# SiLPA_HE_RF_channel_preamp.net
KiCad netlist of a schematic drawn in Altium Designer
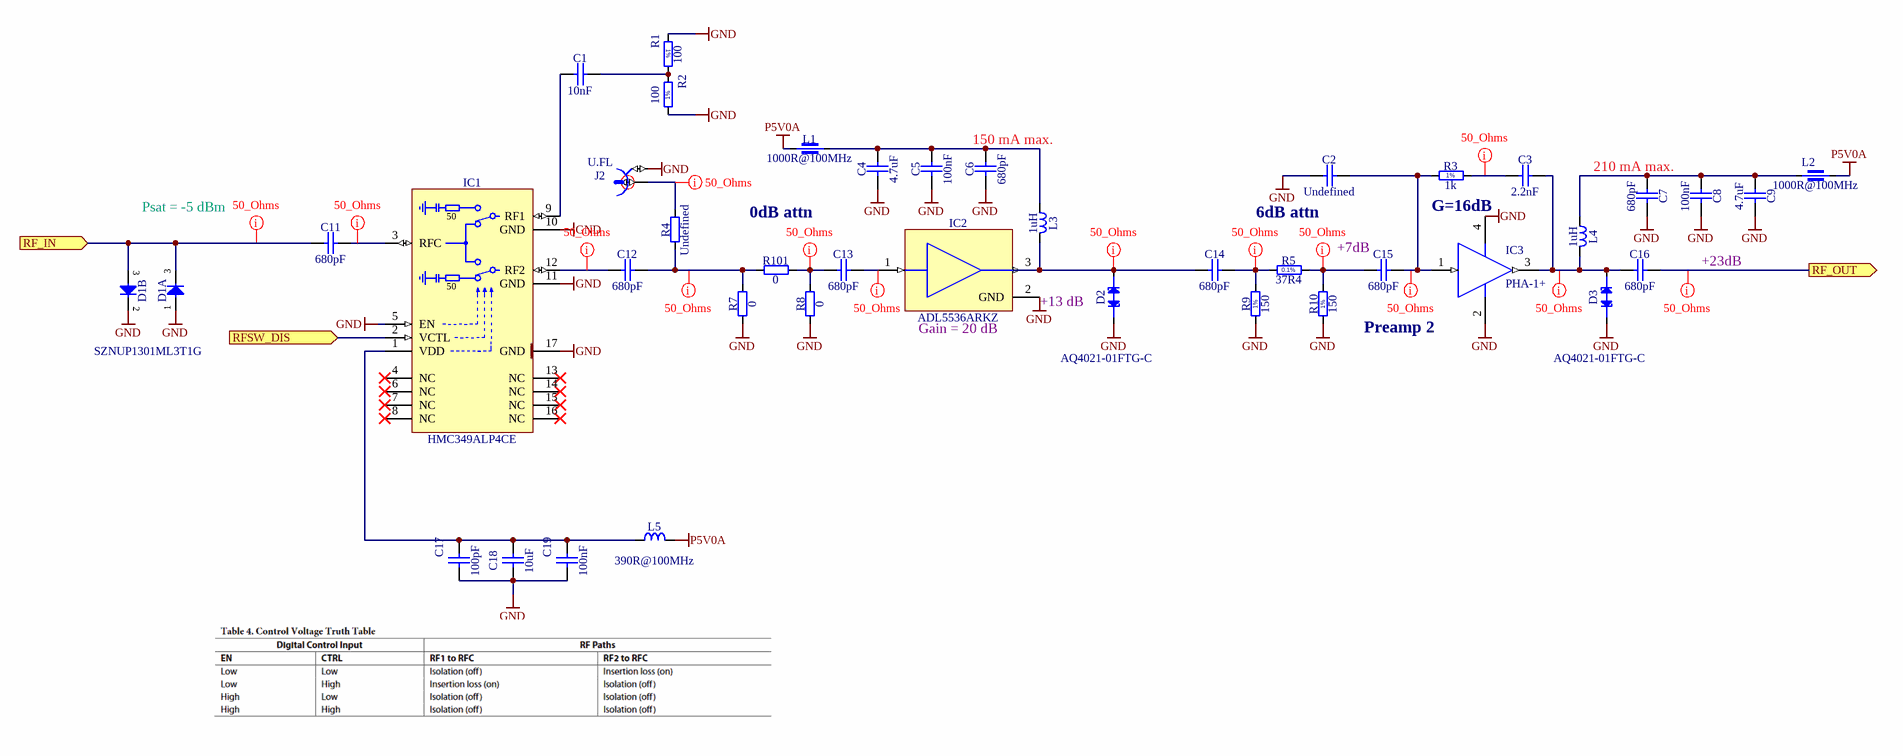
[diagram p0: SiLPA_HE_RF_channel_preamp.SchDoc]

(export (version "E")
  (design (tool "Eeschema 10.0.6"))
  (components
    (comp (ref "C1")
      (value "10nF")
      (footprint "CAPC1005X55N")
      (description "Non-polarised capacitor")
      (fields
        (field (name "PART NUMBER") "CC0402_10NF_16V_10%_X7R")
        (field (name "VOLTAGE") "16V")
        (field (name "AUTHOR") "CERN DEM JLC")
      )
      (libsource (lib "Capacitors") (part "Capacitor - non polarized"))
    )
    (comp (ref "C2")
      (value "Undefined")
      (footprint "CAPC1608X90N")
      (description "Non-polarised capacitor")
      (fields (field (name "PART NUMBER") "CC0603_NO-VALUE") (field (name "AUTHOR") "CERN DEM MR"))
      (libsource (lib "Capacitors") (part "Capacitor - non polarized"))
    )
    (comp (ref "C3")
      (value "2.2nF")
      (footprint "CAPC1608X87N")
      (description "Non-polarised capacitor")
      (fields
        (field (name "PART NUMBER") "CC0603_2.2NF_50V_5%_C0G")
        (field (name "VOLTAGE") "50V")
        (field (name "AUTHOR") "CERN DEM JMW")
      )
      (libsource (lib "Capacitors") (part "Capacitor - non polarized"))
    )
    (comp (ref "C4")
      (value "4.7uF")
      (footprint "CAPC1709X95N")
      (description "Non-polarised capacitor")
      (fields
        (field (name "MANUFACTURER") "GENERIC")
        (field (name "MANUFACTURER PART NUMBER") "CC0603_4.7UF_16V_10%_X5R")
        (field (name "AUTHOR") "CERN DEM JLC")
      )
      (libsource (lib "Capacitors") (part "Capacitor - non polarized"))
    )
    (comp (ref "C5")
      (value "100nF")
      (footprint "CAPC1608X87N")
      (description "Non-polarised capacitor")
      (fields
        (field (name "MANUFACTURER") "GENERIC")
        (field (name "MANUFACTURER PART NUMBER") "CC0603_100NF_50V_10%_X7R")
        (field (name "AUTHOR") "CERN DEM JLC")
      )
      (libsource (lib "Capacitors") (part "Capacitor - non polarized"))
    )
    (comp (ref "C6")
      (value "680pF")
      (footprint "CAPC1608X87N")
      (description "Non-polarised capacitor")
      (fields
        (field (name "PART NUMBER") "CC0603_680PF_50V_5%_NP0")
        (field (name "VOLTAGE") "50V")
        (field (name "AUTHOR") "CERN DEM JLC")
      )
      (libsource (lib "Capacitors") (part "Capacitor - non polarized"))
    )
    (comp (ref "C7")
      (value "680pF")
      (footprint "CAPC1608X87N")
      (description "Non-polarised capacitor")
      (fields
        (field (name "MANUFACTURER") "GENERIC")
        (field (name "MANUFACTURER PART NUMBER") "CC0603_680PF_50V_5%_NP0")
        (field (name "AUTHOR") "CERN DEM JLC")
      )
      (libsource (lib "Capacitors") (part "Capacitor - non polarized"))
    )
    (comp (ref "C8")
      (value "100nF")
      (footprint "CAPC1608X87N")
      (description "Non-polarised capacitor")
      (fields
        (field (name "MANUFACTURER") "GENERIC")
        (field (name "MANUFACTURER PART NUMBER") "CC0603_100NF_50V_10%_X7R")
        (field (name "AUTHOR") "CERN DEM JLC")
      )
      (libsource (lib "Capacitors") (part "Capacitor - non polarized"))
    )
    (comp (ref "C9")
      (value "4.7uF")
      (footprint "CAPC1709X95N")
      (description "Non-polarised capacitor")
      (fields
        (field (name "MANUFACTURER") "GENERIC")
        (field (name "MANUFACTURER PART NUMBER") "CC0603_4.7UF_16V_10%_X5R")
        (field (name "AUTHOR") "CERN DEM JLC")
      )
      (libsource (lib "Capacitors") (part "Capacitor - non polarized"))
    )
    (comp (ref "C11")
      (value "680pF")
      (footprint "CAPC1608X87N")
      (description "Non-polarised capacitor")
      (fields
        (field (name "PART NUMBER") "CC0603_680PF_50V_5%_NP0")
        (field (name "VOLTAGE") "50V")
        (field (name "AUTHOR") "CERN DEM JLC")
      )
      (libsource (lib "Capacitors") (part "Capacitor - non polarized"))
    )
    (comp (ref "C12")
      (value "680pF")
      (footprint "CAPC1608X87N")
      (description "Non-polarised capacitor")
      (fields
        (field (name "PART NUMBER") "CC0603_680PF_50V_5%_NP0")
        (field (name "VOLTAGE") "50V")
        (field (name "AUTHOR") "CERN DEM JLC")
      )
      (libsource (lib "Capacitors") (part "Capacitor - non polarized"))
    )
    (comp (ref "C13")
      (value "680pF")
      (footprint "CAPC1608X87N")
      (description "Non-polarised capacitor")
      (fields
        (field (name "PART NUMBER") "CC0603_680PF_50V_5%_NP0")
        (field (name "VOLTAGE") "50V")
        (field (name "AUTHOR") "CERN DEM JLC")
      )
      (libsource (lib "Capacitors") (part "Capacitor - non polarized"))
    )
    (comp (ref "C14")
      (value "680pF")
      (footprint "CAPC1608X87N")
      (description "Non-polarised capacitor")
      (fields
        (field (name "MANUFACTURER") "GENERIC")
        (field (name "MANUFACTURER PART NUMBER") "CC0603_680PF_50V_5%_NP0")
        (field (name "AUTHOR") "CERN DEM JLC")
      )
      (libsource (lib "SiLPA_HE") (part "CC0603_680PF_50V_5%_NP0"))
    )
    (comp (ref "C15")
      (value "680pF")
      (footprint "CAPC1608X87N")
      (description "Non-polarised capacitor")
      (fields
        (field (name "MANUFACTURER") "GENERIC")
        (field (name "MANUFACTURER PART NUMBER") "CC0603_680PF_50V_5%_NP0")
        (field (name "AUTHOR") "CERN DEM JLC")
      )
      (libsource (lib "Capacitors") (part "Capacitor - non polarized"))
    )
    (comp (ref "C16")
      (value "680pF")
      (footprint "CAPC1608X87N")
      (description "Non-polarised capacitor")
      (fields
        (field (name "MANUFACTURER") "GENERIC")
        (field (name "MANUFACTURER PART NUMBER") "CC0603_680PF_50V_5%_NP0")
        (field (name "AUTHOR") "CERN DEM JLC")
      )
      (libsource (lib "Capacitors") (part "Capacitor - non polarized"))
    )
    (comp (ref "C17")
      (value "100pF")
      (footprint "CAPC1005X55N")
      (description "Non-polarised capacitor")
      (fields
        (field (name "PART NUMBER") "CC0402_100PF_50V_5%_C0G")
        (field (name "VOLTAGE") "50V")
        (field (name "AUTHOR") "CERN DEM JLC")
      )
      (libsource (lib "Capacitors") (part "Capacitor - non polarized"))
    )
    (comp (ref "C18")
      (value "10uF")
      (footprint "CAPC2012X95N")
      (description "Non-polarised capacitor")
      (fields
        (field (name "PART NUMBER") "CC0805_10UF_25V_10%_X5R")
        (field (name "VOLTAGE") "25V")
        (field (name "AUTHOR") "CERN DEM JLC")
      )
      (libsource (lib "SiLPA_HE") (part "CC0805_10UF_25V_10%_X5R"))
    )
    (comp (ref "C19")
      (value "100nF")
      (footprint "CAPC1005X55N")
      (description "Non-polarised capacitor")
      (fields
        (field (name "PART NUMBER") "CC0402_100NF_16V_10%_X5R")
        (field (name "VOLTAGE") "16V")
        (field (name "AUTHOR") "CERN DEM JLC")
      )
      (libsource (lib "Capacitors") (part "Capacitor - non polarized"))
    )
    (comp (ref "D1")
      (value "SZNUP1301ML3T1G")
      (footprint "SOT95P240X110-3N")
      (description "Low Capacitance Diode Array for ESD Protection in a Single Data Line")
      (fields (field (name "VOLTAGE") "70V") (field (name "POWER") "215mA") (field (name "AUTHOR") "GK"))
      (libsource (lib "Diodes") (part "D_TVS_SZNUP1301ML3T1G"))
    )
    (comp (ref "D2")
      (value "AQ4021-01FTG-C")
      (footprint "SOD2513X114N")
      (description "6V Bi-directional,ESD Protection for Transient Voltage Suppressor Diode")
      (fields (field (name "VOLTAGE") "6V") (field (name "POWER") "450W") (field (name "AUTHOR") "GK"))
      (libsource (lib "Diodes") (part "D_TVS_AQ4021-01FTG-C"))
    )
    (comp (ref "D3")
      (value "AQ4021-01FTG-C")
      (footprint "SOD2513X114N")
      (description "6V Bi-directional,ESD Protection for Transient Voltage Suppressor Diode")
      (fields (field (name "VOLTAGE") "6V") (field (name "POWER") "450W") (field (name "AUTHOR") "GK"))
      (libsource (lib "Diodes") (part "D_TVS_AQ4021-01FTG-C"))
    )
    (comp (ref "IC1")
      (value "HMC349ALP4CE")
      (footprint "QFN65P400X400X100-17N-S255")
      (description "DC-4GHz High Isolation SPDT Non-Reflective Switch")
      (fields (field (name "MANUFACTURER") "ANALOG DEVICES") (field (name "AUTHOR") "CERN DEM JLC"))
      (libsource (lib "ICs And Semiconductors") (part "HMC349ALP4CE"))
    )
    (comp (ref "IC2")
      (value "ADL5536ARKZ")
      (footprint "ANALOG-DEVICES_SOT-89(RK-3)")
      (description "20MHz to 1GHz IF Gain Block")
      (fields (field (name "MANUFACTURER") "ANALOG DEVICES") (field (name "AUTHOR") "CERN DEM BC"))
      (libsource (lib "ICs And Semiconductors") (part "ADL5536"))
    )
    (comp (ref "IC3")
      (value "PHA-1+")
      (footprint "MINI-CIRCUITS_DF782")
      (description "Monolithic Amplifier")
      (fields (field (name "MANUFACTURER") "MINI-CIRCUITS") (field (name "AUTHOR") "CERN DEM BC"))
      (libsource (lib "ICs And Semiconductors") (part "Monolithic Amplifier Type 1"))
    )
    (comp (ref "J2")
      (value "U.FL")
      (footprint "HIROSE_U.FL-R-SMT-1(10)")
      (fields
        (field (name "PART NUMBER") "HIROSE_U.FL-R-SMT-1(10)")
        (field (name "MANUFACTURER") "HIROSE (HRS)")
        (field (name "MANUFACTURER PART NUMBER") "U.FL-R-SMT-1(10)")
        (field (name "AUTHOR") "CERN DEM JLC")
      )
      (libsource (lib "Connectors") (part "Coax_1Male_1Shield"))
    )
    (comp (ref "L1")
      (value "1000R@100MHz")
      (footprint "INDC1608X95N")
      (fields
        (field (name "MANUFACTURER") "MURATA")
        (field (name "MANUFACTURER PART NUMBER") "BLM18HE102SN1")
        (field (name "PART NUMBER") "IND0603_MURATA_BLM18HE102SN1")
        (field (name "AUTHOR") "CERN DEM JLC")
      )
      (libsource (lib "Inductors & Transformers") (part "Ferrite Bead"))
    )
    (comp (ref "L2")
      (value "1000R@100MHz")
      (footprint "INDC1608X95N")
      (fields
        (field (name "MANUFACTURER") "MURATA")
        (field (name "MANUFACTURER PART NUMBER") "BLM18HE102SN1")
        (field (name "PART NUMBER") "IND0603_MURATA_BLM18HE102SN1")
        (field (name "AUTHOR") "CERN DEM JLC")
      )
      (libsource (lib "Inductors & Transformers") (part "Ferrite Bead"))
    )
    (comp (ref "L3")
      (value "1uH")
      (footprint "IND_ABRACON_AISC-1008")
      (description "Inductor")
      (fields
        (field (name "PART NUMBER") "IND_1UH_2%_ABRACON_AISC-1008")
        (field (name "POWER") "370mA")
        (field (name "AUTHOR") "CERN DEM BC")
      )
      (libsource (lib "Inductors & Transformers") (part "Inductor"))
    )
    (comp (ref "L4")
      (value "1uH")
      (footprint "IND_ABRACON_AISC-1008")
      (description "Inductor")
      (fields
        (field (name "PART NUMBER") "IND_1UH_2%_ABRACON_AISC-1008")
        (field (name "POWER") "370mA")
        (field (name "AUTHOR") "CERN DEM BC")
      )
      (libsource (lib "Inductors & Transformers") (part "Inductor"))
    )
    (comp (ref "L5")
      (value "390R@100MHz")
      (footprint "INDC1608X95N")
      (description "Inductor")
      (fields
        (field (name "PART NUMBER") "IND0603_TDK_MPZ1608R391A")
        (field (name "POWER") "1.2A")
        (field (name "AUTHOR") "CERN DEM JLC")
      )
      (libsource (lib "") (part "Inductor_1"))
    )
    (comp (ref "R1")
      (value "100")
      (footprint "RESC1005X40N")
      (description "Resistor - 1%")
      (fields
        (field (name "PART NUMBER") "R0402_100R_1%_0.0625W_100PPM")
        (field (name "POWER") "0.0625W")
        (field (name "AUTHOR") "CERN DEM JLC")
      )
      (libsource (lib "Resistors") (part "Resistor - 1%"))
    )
    (comp (ref "R2")
      (value "100")
      (footprint "RESC1005X40N")
      (description "Resistor - 1%")
      (fields
        (field (name "PART NUMBER") "R0402_100R_1%_0.0625W_100PPM")
        (field (name "POWER") "0.0625W")
        (field (name "AUTHOR") "CERN DEM JLC")
      )
      (libsource (lib "Resistors") (part "Resistor - 1%"))
    )
    (comp (ref "R3")
      (value "1k")
      (footprint "RESC1608X55N")
      (description "Resistor - 1%")
      (fields
        (field (name "MANUFACTURER") "GENERIC")
        (field (name "MANUFACTURER PART NUMBER") "R0603_1K_1%_0.1W_100PPM")
        (field (name "AUTHOR") "CERN DEM JLC")
      )
      (libsource (lib "Resistors") (part "Resistor - 1%"))
    )
    (comp (ref "R4")
      (value "Undefined")
      (footprint "RESC1608X55N")
      (description "Resistor")
      (fields
        (field (name "MANUFACTURER PART NUMBER") "R0603_NO-VALUE")
        (field (name "AUTHOR") "CERN DEM JLC")
      )
      (libsource (lib "Resistors") (part "Resistor"))
    )
    (comp (ref "R5")
      (value "37R4")
      (footprint "RESC1608X55N")
      (description "Resistor - 0.1%")
      (fields
        (field (name "MANUFACTURER") "GENERIC")
        (field (name "MANUFACTURER PART NUMBER") "R0603_37R4_0.1%_0.063W_10PPM")
        (field (name "AUTHOR") "CERN DEM JLC")
      )
      (libsource (lib "Resistors") (part "Resistor - 0.1%"))
    )
    (comp (ref "R7")
      (value "0")
      (footprint "RESC1608X55N")
      (description "Resistor")
      (fields
        (field (name "MANUFACTURER") "GENERIC")
        (field (name "MANUFACTURER PART NUMBER") "R0603_0R_JUMPER")
        (field (name "AUTHOR") "CERN DEM JLC")
      )
      (libsource (lib "Resistors") (part "Resistor"))
    )
    (comp (ref "R8")
      (value "0")
      (footprint "RESC1608X55N")
      (description "Resistor")
      (fields
        (field (name "MANUFACTURER") "GENERIC")
        (field (name "MANUFACTURER PART NUMBER") "R0603_0R_JUMPER")
        (field (name "AUTHOR") "CERN DEM JLC")
      )
      (libsource (lib "Resistors") (part "Resistor"))
    )
    (comp (ref "R9")
      (value "150")
      (footprint "RESC1608X55N")
      (description "Resistor - 1%")
      (fields
        (field (name "MANUFACTURER") "GENERIC")
        (field (name "MANUFACTURER PART NUMBER") "R0603_150R_1%_0.1W_100PPM")
        (field (name "AUTHOR") "CERN DEM JLC")
      )
      (libsource (lib "Resistors") (part "Resistor - 1%"))
    )
    (comp (ref "R10")
      (value "150")
      (footprint "RESC1608X55N")
      (description "Resistor - 1%")
      (fields
        (field (name "MANUFACTURER") "GENERIC")
        (field (name "MANUFACTURER PART NUMBER") "R0603_150R_1%_0.1W_100PPM")
        (field (name "AUTHOR") "CERN DEM JLC")
      )
      (libsource (lib "Resistors") (part "Resistor - 1%"))
    )
    (comp (ref "R101")
      (value "0")
      (footprint "RESC1005X40N")
      (description "Resistor")
      (fields
        (field (name "MANUFACTURER") "GENERIC")
        (field (name "MANUFACTURER PART NUMBER") "R0402_0R_JUMPER")
        (field (name "AUTHOR") "CERN DEM JLC")
      )
      (libsource (lib "Resistors") (part "Resistor"))
    )
  )
  (nets
    (net (code "1") (name "/RFSW_DIS") (class "Default")
      (node (ref "IC1") (pin "2") (pinfunction "VCTL_2") (pintype "input"))
    )
    (net (code "2") (name "/RF_IN") (class "Default")
      (node (ref "C11") (pin "1") (pinfunction "1_1") (pintype "passive"))
      (node (ref "D1") (pin "3") (pinfunction "COMAC_3") (pintype "passive"))
    )
    (net (code "3") (name "/RF_OUT") (class "Default")
      (node (ref "C16") (pin "2") (pinfunction "2_2") (pintype "passive"))
    )
    (net (code "4") (name "GND") (class "Default")
      (node (ref "C17") (pin "2") (pinfunction "2_2") (pintype "passive"))
      (node (ref "C18") (pin "1") (pinfunction "1_1") (pintype "passive"))
      (node (ref "C19") (pin "1") (pinfunction "1_1") (pintype "passive"))
      (node (ref "C2") (pin "1") (pinfunction "1_1") (pintype "passive"))
      (node (ref "C4") (pin "1") (pinfunction "1_1") (pintype "passive"))
      (node (ref "C5") (pin "1") (pinfunction "1_1") (pintype "passive"))
      (node (ref "C6") (pin "1") (pinfunction "1_1") (pintype "passive"))
      (node (ref "C7") (pin "1") (pinfunction "1_1") (pintype "passive"))
      (node (ref "C8") (pin "1") (pinfunction "1_1") (pintype "passive"))
      (node (ref "C9") (pin "1") (pinfunction "1_1") (pintype "passive"))
      (node (ref "D1") (pin "1") (pinfunction "A_1") (pintype "passive"))
      (node (ref "D1") (pin "2") (pinfunction "C_2") (pintype "passive"))
      (node (ref "D2") (pin "1") (pinfunction "C_1") (pintype "passive"))
      (node (ref "D3") (pin "1") (pinfunction "C_1") (pintype "passive"))
      (node (ref "IC1") (pin "10") (pinfunction "GND_10") (pintype "power_in"))
      (node (ref "IC1") (pin "11") (pinfunction "GND_11") (pintype "power_in"))
      (node (ref "IC1") (pin "17") (pinfunction "GND_17") (pintype "power_in"))
      (node (ref "IC1") (pin "5") (pinfunction "EN_5") (pintype "input"))
      (node (ref "IC2") (pin "2") (pinfunction "GND_2") (pintype "power_in"))
      (node (ref "IC3") (pin "2") (pinfunction "GND_2") (pintype "power_in"))
      (node (ref "IC3") (pin "4") (pinfunction "GND_4") (pintype "power_in"))
      (node (ref "J2") (pin "2") (pinfunction "2_2") (pintype "bidirectional"))
      (node (ref "R1") (pin "1") (pinfunction "1_1") (pintype "passive"))
      (node (ref "R10") (pin "1") (pinfunction "1_1") (pintype "passive"))
      (node (ref "R2") (pin "1") (pinfunction "1_1") (pintype "passive"))
      (node (ref "R7") (pin "1") (pinfunction "1_1") (pintype "passive"))
      (node (ref "R8") (pin "1") (pinfunction "1_1") (pintype "passive"))
      (node (ref "R9") (pin "1") (pinfunction "1_1") (pintype "passive"))
    )
    (net (code "5") (name "Net-(C1-Pad2)") (class "Default")
      (node (ref "C1") (pin "2") (pinfunction "2_2") (pintype "passive"))
      (node (ref "R1") (pin "2") (pinfunction "2_2") (pintype "passive"))
      (node (ref "R2") (pin "2") (pinfunction "2_2") (pintype "passive"))
    )
    (net (code "6") (name "Net-(C3-Pad1)") (class "Default")
      (node (ref "C3") (pin "1") (pinfunction "1_1") (pintype "passive"))
      (node (ref "R3") (pin "2") (pinfunction "2_2") (pintype "passive"))
    )
    (net (code "7") (name "Net-(C4-Pad2)") (class "Default")
      (node (ref "C4") (pin "2") (pinfunction "2_2") (pintype "passive"))
      (node (ref "C5") (pin "2") (pinfunction "2_2") (pintype "passive"))
      (node (ref "C6") (pin "2") (pinfunction "2_2") (pintype "passive"))
      (node (ref "L1") (pin "2") (pinfunction "2_2") (pintype "passive"))
      (node (ref "L3") (pin "1") (pinfunction "1_1") (pintype "passive"))
    )
    (net (code "8") (name "Net-(C7-Pad2)") (class "Default")
      (node (ref "C7") (pin "2") (pinfunction "2_2") (pintype "passive"))
      (node (ref "C8") (pin "2") (pinfunction "2_2") (pintype "passive"))
      (node (ref "C9") (pin "2") (pinfunction "2_2") (pintype "passive"))
      (node (ref "L2") (pin "1") (pinfunction "1_1") (pintype "passive"))
      (node (ref "L4") (pin "1") (pinfunction "1_1") (pintype "passive"))
    )
    (net (code "9") (name "Net-(C12-Pad2)") (class "Default")
      (node (ref "C12") (pin "2") (pinfunction "2_2") (pintype "passive"))
      (node (ref "R101") (pin "1") (pinfunction "1_1") (pintype "passive"))
      (node (ref "R4") (pin "2") (pinfunction "2_2") (pintype "passive"))
      (node (ref "R7") (pin "2") (pinfunction "2_2") (pintype "passive"))
    )
    (net (code "10") (name "Net-(C13-Pad1)") (class "Default")
      (node (ref "C13") (pin "1") (pinfunction "1_1") (pintype "passive"))
      (node (ref "R101") (pin "2") (pinfunction "2_2") (pintype "passive"))
      (node (ref "R8") (pin "2") (pinfunction "2_2") (pintype "passive"))
    )
    (net (code "11") (name "Net-(C14-Pad2)") (class "Default")
      (node (ref "C14") (pin "2") (pinfunction "2_2") (pintype "passive"))
      (node (ref "R5") (pin "1") (pinfunction "1_1") (pintype "passive"))
      (node (ref "R9") (pin "2") (pinfunction "2_2") (pintype "passive"))
    )
    (net (code "12") (name "Net-(C15-Pad1)") (class "Default")
      (node (ref "C15") (pin "1") (pinfunction "1_1") (pintype "passive"))
      (node (ref "R10") (pin "2") (pinfunction "2_2") (pintype "passive"))
      (node (ref "R5") (pin "2") (pinfunction "2_2") (pintype "passive"))
    )
    (net (code "13") (name "Net-(D2-A)") (class "Default")
      (node (ref "C14") (pin "1") (pinfunction "1_1") (pintype "passive"))
      (node (ref "D2") (pin "2") (pinfunction "A_2") (pintype "passive"))
      (node (ref "IC2") (pin "3") (pinfunction "RFOUT_3") (pintype "output"))
      (node (ref "L3") (pin "2") (pinfunction "2_2") (pintype "passive"))
    )
    (net (code "14") (name "Net-(D3-A)") (class "Default")
      (node (ref "C16") (pin "1") (pinfunction "1_1") (pintype "passive"))
      (node (ref "C3") (pin "2") (pinfunction "2_2") (pintype "passive"))
      (node (ref "D3") (pin "2") (pinfunction "A_2") (pintype "passive"))
      (node (ref "IC3") (pin "3") (pinfunction "RF_OUT_3") (pintype "output"))
      (node (ref "L4") (pin "2") (pinfunction "2_2") (pintype "passive"))
    )
    (net (code "15") (name "Net-(IC1-RF1)") (class "Default")
      (node (ref "C1") (pin "1") (pinfunction "1_1") (pintype "passive"))
      (node (ref "IC1") (pin "9") (pinfunction "RF1_9") (pintype "bidirectional"))
    )
    (net (code "16") (name "Net-(IC1-RF2)") (class "Default")
      (node (ref "C12") (pin "1") (pinfunction "1_1") (pintype "passive"))
      (node (ref "IC1") (pin "12") (pinfunction "RF2_12") (pintype "bidirectional"))
    )
    (net (code "17") (name "Net-(IC1-RFC)") (class "Default")
      (node (ref "C11") (pin "2") (pinfunction "2_2") (pintype "passive"))
      (node (ref "IC1") (pin "3") (pinfunction "RFC_3") (pintype "bidirectional"))
    )
    (net (code "18") (name "Net-(IC1-VDD)") (class "Default")
      (node (ref "C17") (pin "1") (pinfunction "1_1") (pintype "passive"))
      (node (ref "C18") (pin "2") (pinfunction "2_2") (pintype "passive"))
      (node (ref "C19") (pin "2") (pinfunction "2_2") (pintype "passive"))
      (node (ref "IC1") (pin "1") (pinfunction "VDD_1") (pintype "power_in"))
      (node (ref "L5") (pin "1") (pinfunction "1_1") (pintype "passive"))
    )
    (net (code "19") (name "Net-(IC2-RFIN)") (class "Default")
      (node (ref "C13") (pin "2") (pinfunction "2_2") (pintype "passive"))
      (node (ref "IC2") (pin "1") (pinfunction "RFIN_1") (pintype "input"))
    )
    (net (code "20") (name "Net-(IC3-RF_IN)") (class "Default")
      (node (ref "C15") (pin "2") (pinfunction "2_2") (pintype "passive"))
      (node (ref "C2") (pin "2") (pinfunction "2_2") (pintype "passive"))
      (node (ref "IC3") (pin "1") (pinfunction "RF_IN_1") (pintype "input"))
      (node (ref "R3") (pin "1") (pinfunction "1_1") (pintype "passive"))
    )
    (net (code "21") (name "Net-(J2-Pad1)") (class "Default")
      (node (ref "J2") (pin "1") (pinfunction "1_1") (pintype "bidirectional"))
      (node (ref "R4") (pin "1") (pinfunction "1_1") (pintype "passive"))
    )
    (net (code "22") (name "P5V0A") (class "Default")
      (node (ref "L1") (pin "1") (pinfunction "1_1") (pintype "passive"))
      (node (ref "L2") (pin "2") (pinfunction "2_2") (pintype "passive"))
      (node (ref "L5") (pin "2") (pinfunction "2_2") (pintype "passive"))
    )
    (net (code "23") (name "unconnected-(IC1-NC-Pad4)") (class "Default")
      (node (ref "IC1") (pin "4") (pinfunction "NC_4") (pintype "passive+no_connect"))
    )
    (net (code "24") (name "unconnected-(IC1-NC-Pad6)") (class "Default")
      (node (ref "IC1") (pin "6") (pinfunction "NC_6") (pintype "passive+no_connect"))
    )
    (net (code "25") (name "unconnected-(IC1-NC-Pad7)") (class "Default")
      (node (ref "IC1") (pin "7") (pinfunction "NC_7") (pintype "passive+no_connect"))
    )
    (net (code "26") (name "unconnected-(IC1-NC-Pad8)") (class "Default")
      (node (ref "IC1") (pin "8") (pinfunction "NC_8") (pintype "passive+no_connect"))
    )
    (net (code "27") (name "unconnected-(IC1-NC-Pad13)") (class "Default")
      (node (ref "IC1") (pin "13") (pinfunction "NC_13") (pintype "passive+no_connect"))
    )
    (net (code "28") (name "unconnected-(IC1-NC-Pad14)") (class "Default")
      (node (ref "IC1") (pin "14") (pinfunction "NC_14") (pintype "passive+no_connect"))
    )
    (net (code "29") (name "unconnected-(IC1-NC-Pad15)") (class "Default")
      (node (ref "IC1") (pin "15") (pinfunction "NC_15") (pintype "passive+no_connect"))
    )
    (net (code "30") (name "unconnected-(IC1-NC-Pad16)") (class "Default")
      (node (ref "IC1") (pin "16") (pinfunction "NC_16") (pintype "passive+no_connect"))
    )
  )
)
